# STM32-G0-Dip-Module.net
KiCad netlist of a schematic drawn in EAGLE
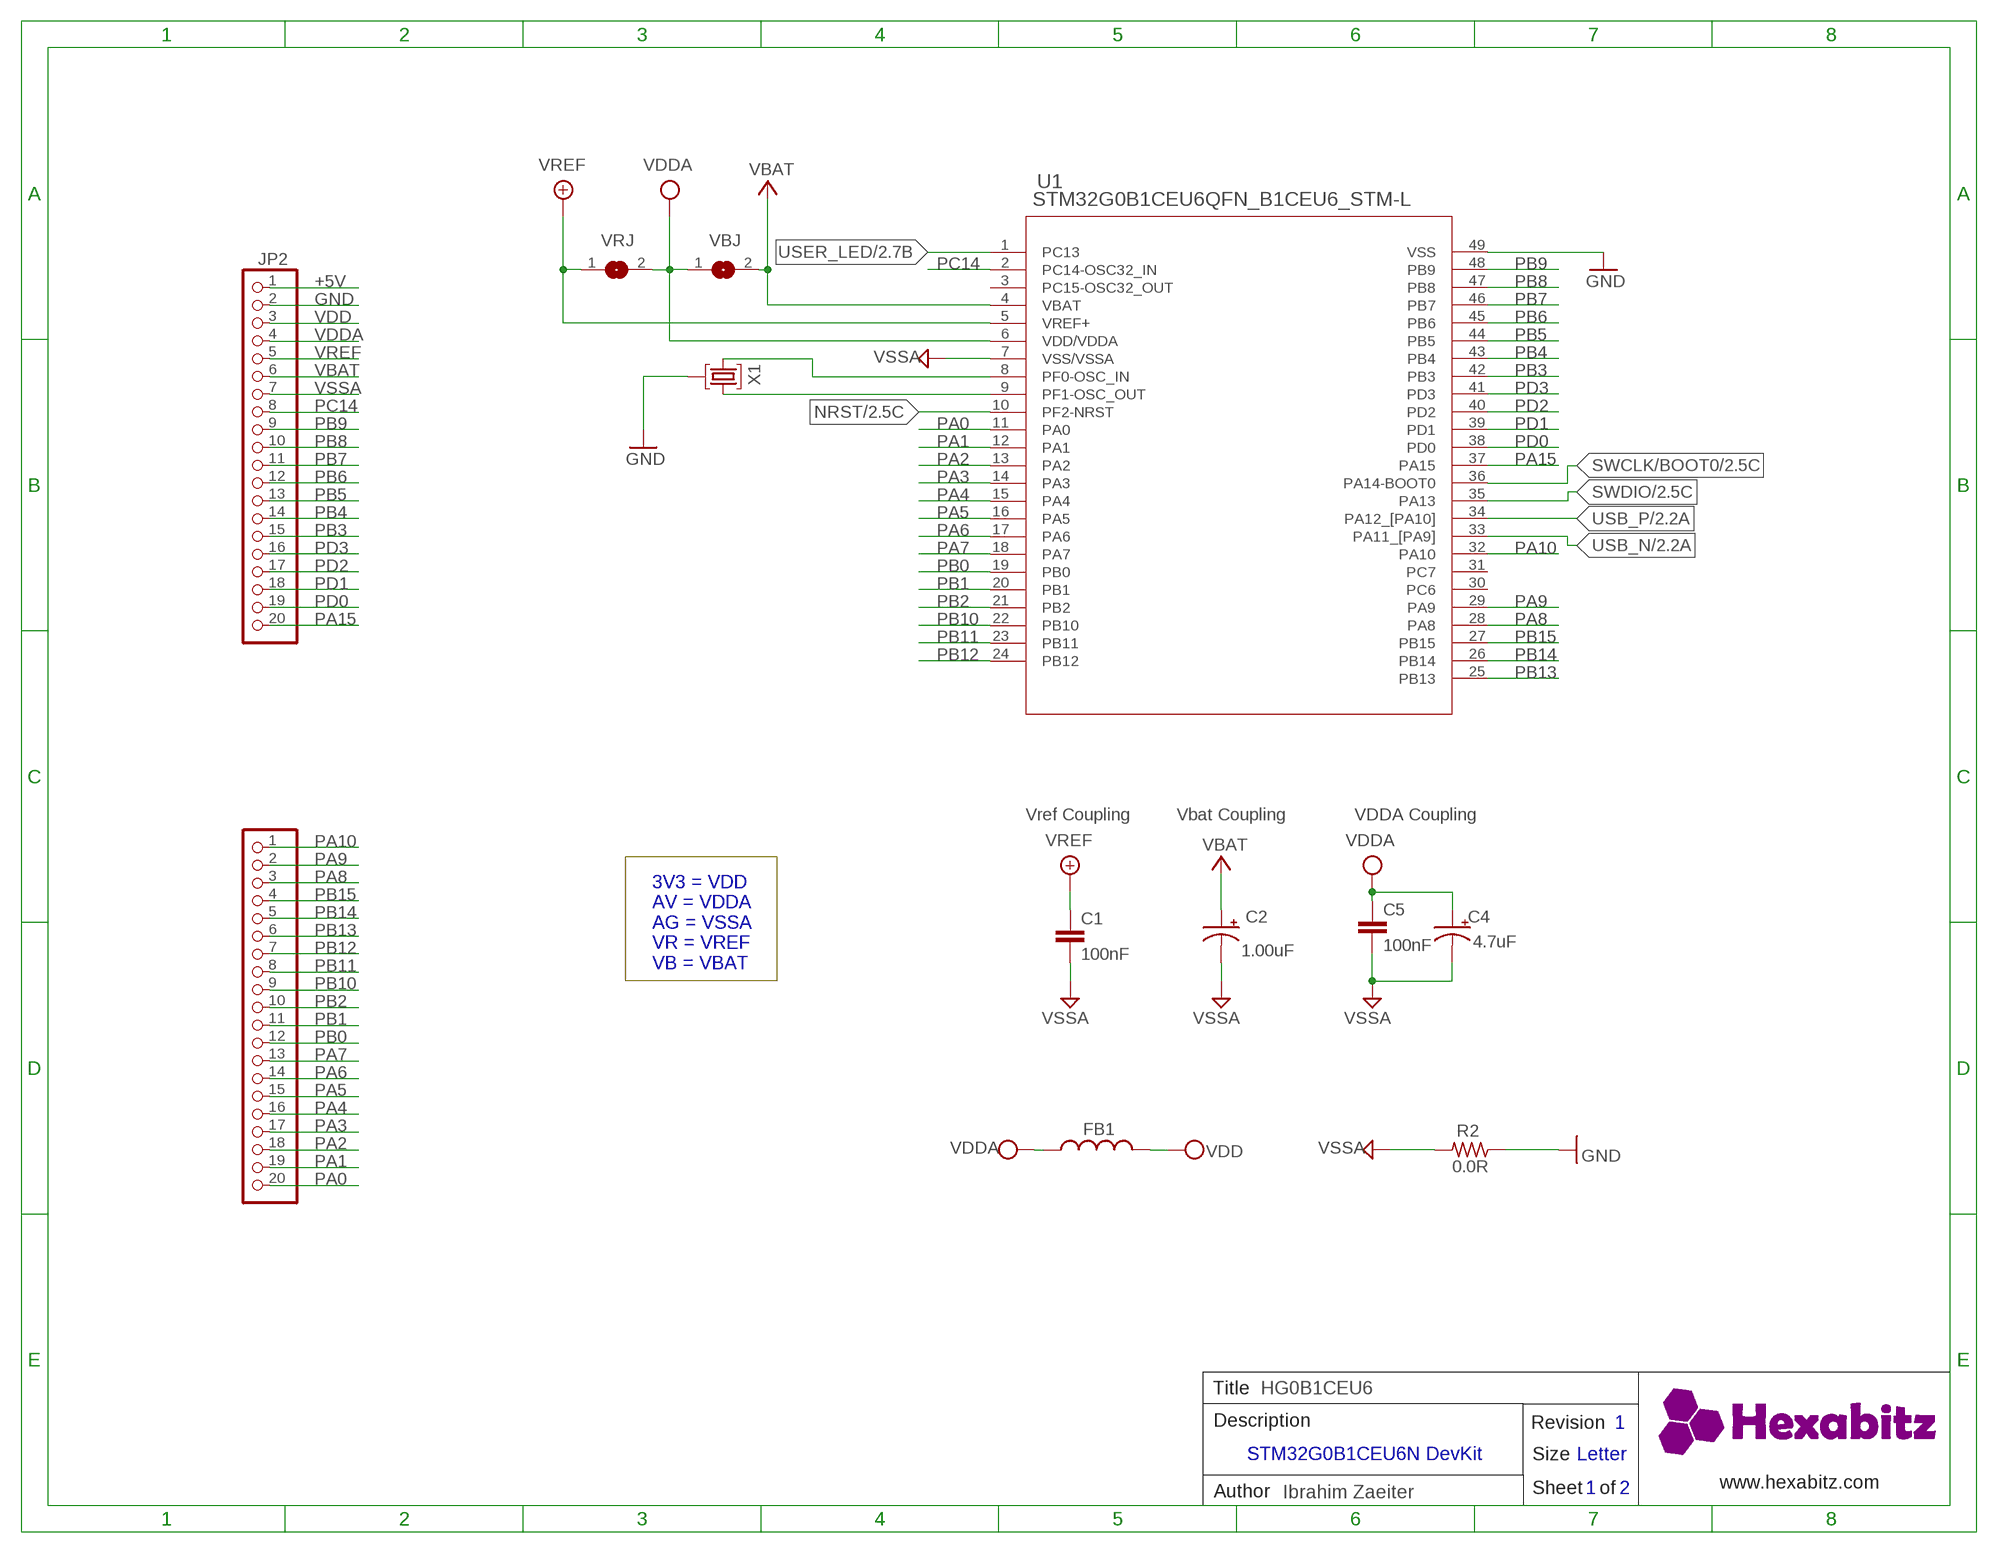
[diagram p0: schematic, sheet 1]
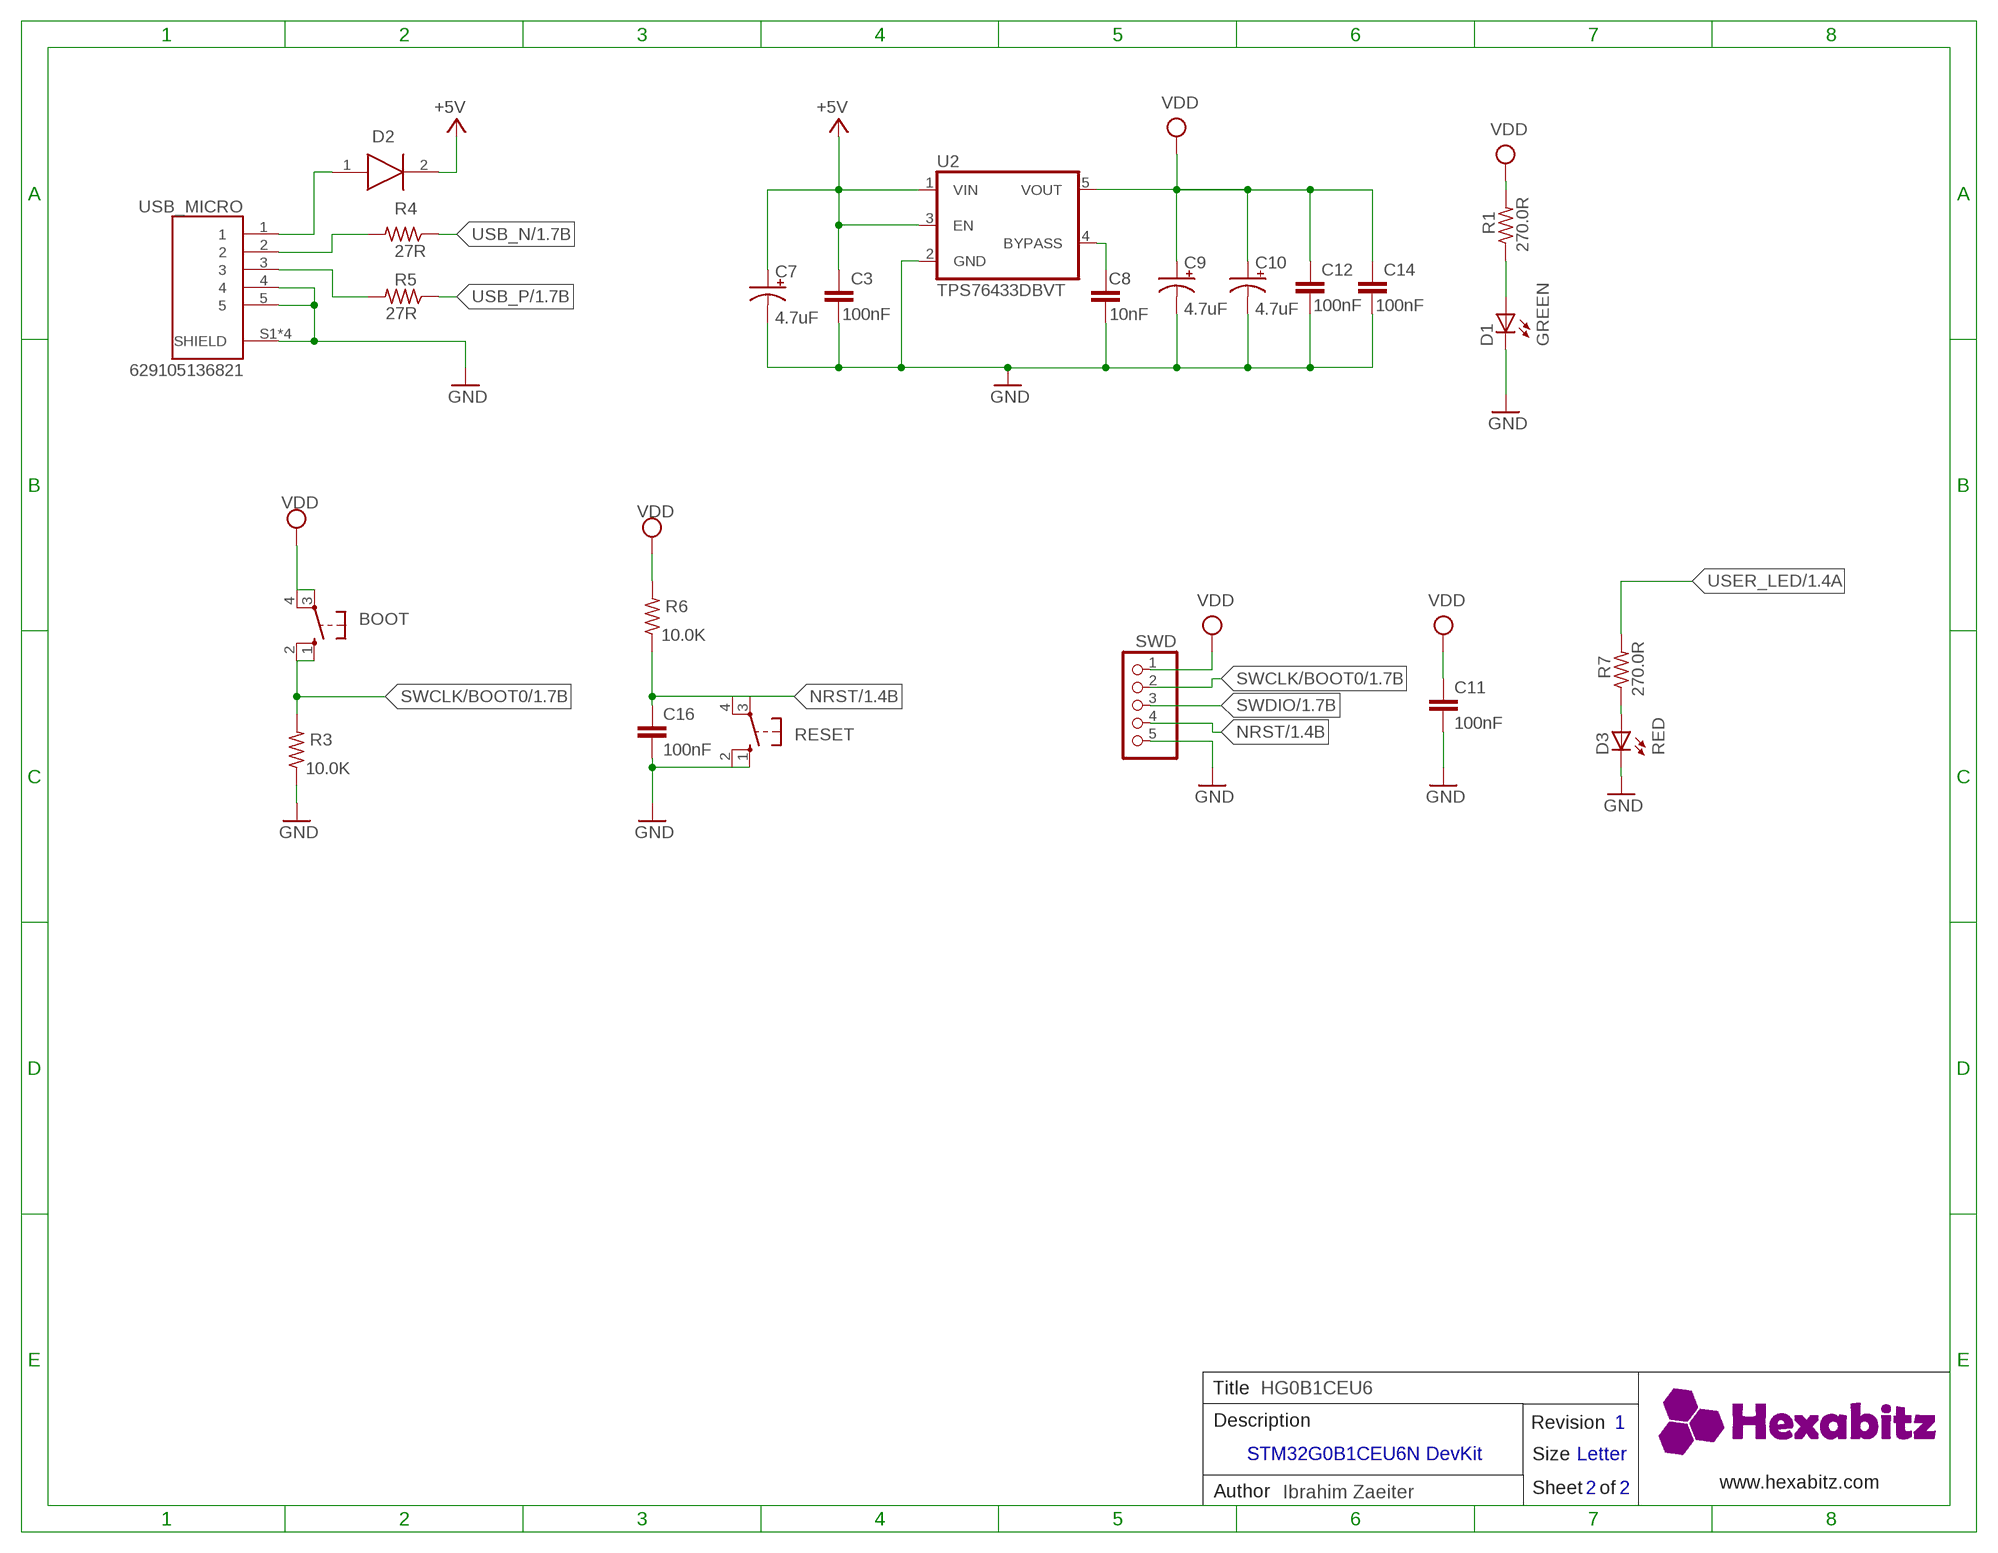
[diagram p1: schematic, sheet 2]

(export (version "E")
  (design (tool "Eeschema 10.0.6"))
  (components
    (comp (ref "C1")
      (value "100nF")
      (footprint "eagle-import:C-0603")
      (fields
        (field (name "CAPACITANCE") "100nF")
        (field (name "MFN") "KEMET")
        (field (name "MPN") "C0603C104K8RACTU")
        (field (name "OCTOPART_URL") "https://octopart.com/c0603c104k8ractu-kemet-145075?r=sp&s=9bS9ASSwSEqMCE9KBEQZ0g")
        (field (name "TOLERANCE") "10%")
        (field (name "VOLTAGE_RATING") "10V")
      )
      (libsource (lib "eagle-import") (part "C-0603"))
    )
    (comp (ref "C2")
      (value "1.00uF")
      (footprint "eagle-import:C-0805-POL")
      (fields
        (field (name "CAPACITANCE") "1.00uF")
        (field (name "MFN") "Yageo")
        (field (name "MPN") "CC0805KKX7R7BB105")
        (field (name "OCTOPART_URL") "https://octopart.com/cc0805kkx7r7bb105-yageo-8376555?r=sp&s=YKl1wwtkROau_X5nniH2ig")
        (field (name "TOLERANCE") "10%")
        (field (name "VOLTAGE_RATING") "16V")
      )
      (libsource (lib "eagle-import") (part "C-0805-POL"))
    )
    (comp (ref "C4")
      (value "4.7uF")
      (footprint "eagle-import:C-0805-POL")
      (fields
        (field (name "CAPACITANCE") "4.7uF")
        (field (name "MFN") "Murata")
        (field (name "MPN") "GRM21BC81E475KA12L")
        (field (name "OCTOPART_URL") "https://octopart.com/grm21bc81e475ka12l-murata-10331911?r=sp&s=RY3qZSD8T6mG6TC9CHI5qQ")
        (field (name "TOLERANCE") "10%")
        (field (name "VOLTAGE_RATING") "25V")
      )
      (libsource (lib "eagle-import") (part "C-0805-POL"))
    )
    (comp (ref "C5")
      (value "100nF")
      (footprint "eagle-import:C-0603")
      (fields
        (field (name "CAPACITANCE") "100nF")
        (field (name "MFN") "KEMET")
        (field (name "MPN") "C0603C104K8RACTU")
        (field (name "OCTOPART_URL") "https://octopart.com/c0603c104k8ractu-kemet-145075?r=sp&s=9bS9ASSwSEqMCE9KBEQZ0g")
        (field (name "TOLERANCE") "10%")
        (field (name "VOLTAGE_RATING") "10")
      )
      (libsource (lib "eagle-import") (part "C-0603"))
    )
    (comp (ref "FB1")
      (value "FB-TDK_MMZ1608Y300B")
      (footprint "eagle-import:FB-TDK_MMZ1608Y300B")
      (fields
        (field (name "MFN") "TDK ")
        (field (name "MPN") "MMZ1608Y300B")
        (field (name "OCTOPART_URL") "https://octopart.com/mmz1608y300b-tdk-368280?r=sp&s=cd9_2ZEqQ9q9UNBuQgHAiA")
      )
      (libsource (lib "eagle-import") (part "FB-TDK_MMZ1608Y300B"))
    )
    (comp (ref "JP1")
      (value "PINHD-1X20")
      (footprint "eagle-import:1X20")
      (libsource (lib "eagle-import") (part "PINHD-1X20"))
    )
    (comp (ref "JP2")
      (value "PINHD-1X20")
      (footprint "eagle-import:1X20")
      (libsource (lib "eagle-import") (part "PINHD-1X20"))
    )
    (comp (ref "R2")
      (value "0.0R")
      (footprint "eagle-import:R-0603")
      (fields
        (field (name "MFN") "Yageo")
        (field (name "MPN") "RC0603JR-070RL")
        (field (name "OCTOPART_URL") "https://octopart.com/rc0603jr-070rl-yageo-1241539?r=sp&s=X2NteqRjRNWrnx42Y0aliA")
        (field (name "RESISTANCE") "0.0 Ohm")
      )
      (libsource (lib "eagle-import") (part "R-0603"))
    )
    (comp (ref "U1")
      (value "STM32G0B1CEU6QFN_B1CEU6_STM-L")
      (footprint "eagle-import:QFN_B1CEU6_STM-L")
      (fields
        (field (name "MANUFACTURER_PART_NUMBER") "STM32G0B1CEU6")
        (field (name "COPYRIGHT") "Copyright (C) 2021 Ultra Librarian. All rights reserved.")
      )
      (libsource (lib "eagle-import") (part "STM32G0B1CEU6QFN_B1CEU6_STM-L"))
    )
    (comp (ref "VBJ") (value "SJ") (footprint "eagle-import:SJ") (libsource (lib "eagle-import") (part "SJ")))
    (comp (ref "VRJ") (value "SJ") (footprint "eagle-import:SJ") (libsource (lib "eagle-import") (part "SJ")))
    (comp (ref "X1")
      (value "XTALL_CSTCE8M00G52")
      (footprint "eagle-import:XTALL_CSTCE8M00G52")
      (fields (field (name "MPN") "CSTCE8M00G52Z-R0"))
      (libsource (lib "eagle-import") (part "XTALL_CSTCE8M00G52"))
    )
    (comp (ref "BOOT")
      (value "10-XX")
      (footprint "eagle-import:B3F-10XX")
      (fields (field (name "MPN") "B3F-1000"))
      (libsource (lib "eagle-import") (part "10-XX"))
    )
    (comp (ref "C3")
      (value "100nF")
      (footprint "eagle-import:C-0603")
      (fields
        (field (name "CAPACITANCE") "100nF")
        (field (name "MFN") "KEMET")
        (field (name "MPN") "C0603C104K8RACTU")
        (field (name "OCTOPART_URL") "https://octopart.com/c0603c104k8ractu-kemet-145075?r=sp&s=9bS9ASSwSEqMCE9KBEQZ0g")
        (field (name "TOLERANCE") "10%")
        (field (name "VOLTAGE_RATING") "10")
      )
      (libsource (lib "eagle-import") (part "C-0603"))
    )
    (comp (ref "C7")
      (value "4.7uF")
      (footprint "eagle-import:C-0805-POL")
      (fields
        (field (name "CAPACITANCE") "4.7uF")
        (field (name "MFN") "Murata")
        (field (name "MPN") "GRM21BC81E475KA12L")
        (field (name "OCTOPART_URL") "https://octopart.com/grm21bc81e475ka12l-murata-10331911?r=sp&s=RY3qZSD8T6mG6TC9CHI5qQ")
        (field (name "TOLERANCE") "10%")
        (field (name "VOLTAGE_RATING") "25V")
      )
      (libsource (lib "eagle-import") (part "C-0805-POL"))
    )
    (comp (ref "C8")
      (value "10nF")
      (footprint "eagle-import:C-0603")
      (fields
        (field (name "CAPACITANCE") "100nF")
        (field (name "MFN") "KEMET")
        (field (name "MPN") "C0603C104K8RACTU")
        (field (name "OCTOPART_URL") "https://octopart.com/c0603c104k8ractu-kemet-145075?r=sp&s=9bS9ASSwSEqMCE9KBEQZ0g")
        (field (name "TOLERANCE") "10%")
        (field (name "VOLTAGE_RATING") "10")
      )
      (libsource (lib "eagle-import") (part "C-0603"))
    )
    (comp (ref "C9")
      (value "4.7uF")
      (footprint "eagle-import:C-0805-POL")
      (fields
        (field (name "CAPACITANCE") "4.7uF")
        (field (name "MFN") "Murata")
        (field (name "MPN") "GRM21BC81E475KA12L")
        (field (name "OCTOPART_URL") "https://octopart.com/grm21bc81e475ka12l-murata-10331911?r=sp&s=RY3qZSD8T6mG6TC9CHI5qQ")
        (field (name "TOLERANCE") "10%")
        (field (name "VOLTAGE_RATING") "25V")
      )
      (libsource (lib "eagle-import") (part "C-0805-POL"))
    )
    (comp (ref "C10")
      (value "4.7uF")
      (footprint "eagle-import:C-0805-POL")
      (fields
        (field (name "CAPACITANCE") "4.7uF")
        (field (name "MFN") "Murata")
        (field (name "MPN") "GRM21BC81E475KA12L")
        (field (name "OCTOPART_URL") "https://octopart.com/grm21bc81e475ka12l-murata-10331911?r=sp&s=RY3qZSD8T6mG6TC9CHI5qQ")
        (field (name "TOLERANCE") "10%")
        (field (name "VOLTAGE_RATING") "25V")
      )
      (libsource (lib "eagle-import") (part "C-0805-POL"))
    )
    (comp (ref "C11")
      (value "100nF")
      (footprint "eagle-import:C-0603")
      (fields
        (field (name "CAPACITANCE") "100nF")
        (field (name "MFN") "KEMET")
        (field (name "MPN") "C0603C104K8RACTU")
        (field (name "OCTOPART_URL") "https://octopart.com/c0603c104k8ractu-kemet-145075?r=sp&s=9bS9ASSwSEqMCE9KBEQZ0g")
        (field (name "TOLERANCE") "10%")
        (field (name "VOLTAGE_RATING") "10V")
      )
      (libsource (lib "eagle-import") (part "C-0603"))
    )
    (comp (ref "C12")
      (value "100nF")
      (footprint "eagle-import:C-0603")
      (fields
        (field (name "CAPACITANCE") "100nF")
        (field (name "MFN") "KEMET")
        (field (name "MPN") "C0603C104K8RACTU")
        (field (name "OCTOPART_URL") "https://octopart.com/c0603c104k8ractu-kemet-145075?r=sp&s=9bS9ASSwSEqMCE9KBEQZ0g")
        (field (name "TOLERANCE") "10%")
        (field (name "VOLTAGE_RATING") "10")
      )
      (libsource (lib "eagle-import") (part "C-0603"))
    )
    (comp (ref "C14")
      (value "100nF")
      (footprint "eagle-import:C-0603")
      (fields
        (field (name "CAPACITANCE") "100nF")
        (field (name "MFN") "KEMET")
        (field (name "MPN") "C0603C104K8RACTU")
        (field (name "OCTOPART_URL") "https://octopart.com/c0603c104k8ractu-kemet-145075?r=sp&s=9bS9ASSwSEqMCE9KBEQZ0g")
        (field (name "TOLERANCE") "10%")
        (field (name "VOLTAGE_RATING") "10")
      )
      (libsource (lib "eagle-import") (part "C-0603"))
    )
    (comp (ref "C16")
      (value "100nF")
      (footprint "eagle-import:C-0603")
      (fields
        (field (name "CAPACITANCE") "100nF")
        (field (name "MFN") "KEMET")
        (field (name "MPN") "C0603C104K8RACTU")
        (field (name "OCTOPART_URL") "https://octopart.com/c0603c104k8ractu-kemet-145075?r=sp&s=9bS9ASSwSEqMCE9KBEQZ0g")
        (field (name "TOLERANCE") "10%")
        (field (name "VOLTAGE_RATING") "10V")
      )
      (libsource (lib "eagle-import") (part "C-0603"))
    )
    (comp (ref "D1")
      (value "GREEN")
      (footprint "eagle-import:VLMS1300-GS08")
      (fields
        (field (name "MPN") "VLMS1300-GS08")
        (field (name "MFN") "Vishay")
        (field (name "MPN_1") "VLMS1300-GS08")
        (field (name "OCTOPART_URL") "https://octopart.com/vlms1300-gs08-vishay-21709201?r=sp&s=_gcP4_q8T1SC6PJQPTQ9yA")
      )
      (libsource (lib "eagle-import") (part "VLMS1300-GS08"))
    )
    (comp (ref "D2")
      (value "FSM17PL-TP")
      (footprint "eagle-import:FSM17PL-TP")
      (libsource (lib "eagle-import") (part "FSM17PL-TP"))
    )
    (comp (ref "D3")
      (value "RED")
      (footprint "eagle-import:VLMS1300-GS08")
      (fields
        (field (name "MPN") "VLMS1300-GS08")
        (field (name "MFN") "Vishay")
        (field (name "MPN_1") "VLMS1300-GS08")
        (field (name "OCTOPART_URL") "https://octopart.com/vlms1300-gs08-vishay-21709201?r=sp&s=_gcP4_q8T1SC6PJQPTQ9yA")
      )
      (libsource (lib "eagle-import") (part "VLMS1300-GS08"))
    )
    (comp (ref "R1")
      (value "270.0R")
      (footprint "eagle-import:R-0603")
      (fields
        (field (name "MFN") "Yageo")
        (field (name "MPN") "RC0603FR-07270RL")
        (field (name "OCTOPART_URL") "https://octopart.com/search?q=RC0603FR-07270RL&start=0")
        (field (name "RESISTANCE") "270.0 Ohm")
        (field (name "TOLERANCE") "1%")
      )
      (libsource (lib "eagle-import") (part "R-0603"))
    )
    (comp (ref "R3")
      (value "10.0K")
      (footprint "eagle-import:R-0603")
      (fields
        (field (name "MFN") "Yageo")
        (field (name "MPN") "RC0603JR-0710KL")
        (field (name "OCTOPART_URL") "https://octopart.com/search?q=RC0603JR-0710KL&start=0")
        (field (name "RESISTANCE") "10.0K Ohm")
        (field (name "TOLERANCE") "5%")
      )
      (libsource (lib "eagle-import") (part "R-0603"))
    )
    (comp (ref "R4")
      (value "27R")
      (footprint "eagle-import:R-0603")
      (fields
        (field (name "MFN") "Yageo")
        (field (name "MPN") "RC0603JR-0710KL")
        (field (name "OCTOPART_URL") "https://octopart.com/search?q=RC0603JR-0710KL&start=0")
        (field (name "RESISTANCE") "10.0K Ohm")
        (field (name "TOLERANCE") "5%")
      )
      (libsource (lib "eagle-import") (part "R-0603"))
    )
    (comp (ref "R5")
      (value "27R")
      (footprint "eagle-import:R-0603")
      (fields
        (field (name "MFN") "Yageo")
        (field (name "MPN") "RC0603JR-0710KL")
        (field (name "OCTOPART_URL") "https://octopart.com/search?q=RC0603JR-0710KL&start=0")
        (field (name "RESISTANCE") "10.0K Ohm")
        (field (name "TOLERANCE") "5%")
      )
      (libsource (lib "eagle-import") (part "R-0603"))
    )
    (comp (ref "R6")
      (value "10.0K")
      (footprint "eagle-import:R-0603")
      (fields
        (field (name "MFN") "Yageo")
        (field (name "MPN") "RC0603JR-0710KL")
        (field (name "OCTOPART_URL") "https://octopart.com/search?q=RC0603JR-0710KL&start=0")
        (field (name "RESISTANCE") "10.0K Ohm")
        (field (name "TOLERANCE") "5%")
      )
      (libsource (lib "eagle-import") (part "R-0603"))
    )
    (comp (ref "R7")
      (value "270.0R")
      (footprint "eagle-import:R-0603")
      (fields
        (field (name "MFN") "Yageo")
        (field (name "MPN") "RC0603FR-07270RL")
        (field (name "OCTOPART_URL") "https://octopart.com/search?q=RC0603FR-07270RL&start=0")
        (field (name "RESISTANCE") "270.0 Ohm")
        (field (name "TOLERANCE") "1%")
      )
      (libsource (lib "eagle-import") (part "R-0603"))
    )
    (comp (ref "RESET")
      (value "10-XX")
      (footprint "eagle-import:B3F-10XX")
      (fields (field (name "MPN") "B3F-1000"))
      (libsource (lib "eagle-import") (part "10-XX"))
    )
    (comp (ref "SWD")
      (value "PINHD-1X5/90")
      (footprint "eagle-import:1X05_90")
      (libsource (lib "eagle-import") (part "PINHD-1X5/90"))
    )
    (comp (ref "U2")
      (value "TPS76433DBVT")
      (footprint "eagle-import:SOT25")
      (libsource (lib "eagle-import") (part "TPS764DBVT33"))
    )
    (comp (ref "USB_MICRO")
      (value "629105136821")
      (footprint "eagle-import:WE_629105136821")
      (fields (field (name "MF") "Würth Elektronik"))
      (libsource (lib "eagle-import") (part "629105136821"))
    )
  )
  (nets
    (net (code "1") (name "+5V") (class "Default")
      (node (ref "C3") (pin "1") (pinfunction "1_1") (pintype "passive"))
      (node (ref "C7") (pin "1") (pinfunction "+_1") (pintype "passive"))
      (node (ref "D2") (pin "2") (pinfunction "K_2") (pintype "bidirectional"))
      (node (ref "JP2") (pin "1") (pinfunction "1_1") (pintype "passive"))
      (node (ref "U2") (pin "1") (pinfunction "VIN_1") (pintype "input"))
      (node (ref "U2") (pin "3") (pinfunction "EN_3") (pintype "input"))
    )
    (net (code "2") (name "GND") (class "Default")
      (node (ref "C10") (pin "2") (pinfunction "-_2") (pintype "passive"))
      (node (ref "C11") (pin "2") (pinfunction "2_2") (pintype "passive"))
      (node (ref "C12") (pin "2") (pinfunction "2_2") (pintype "passive"))
      (node (ref "C14") (pin "2") (pinfunction "2_2") (pintype "passive"))
      (node (ref "C16") (pin "2") (pinfunction "2_2") (pintype "passive"))
      (node (ref "C3") (pin "2") (pinfunction "2_2") (pintype "passive"))
      (node (ref "C7") (pin "2") (pinfunction "-_2") (pintype "passive"))
      (node (ref "C8") (pin "2") (pinfunction "2_2") (pintype "passive"))
      (node (ref "C9") (pin "2") (pinfunction "-_2") (pintype "passive"))
      (node (ref "D1") (pin "C") (pinfunction "C_C") (pintype "passive"))
      (node (ref "D3") (pin "C") (pinfunction "C_C") (pintype "passive"))
      (node (ref "JP2") (pin "2") (pinfunction "2_2") (pintype "passive"))
      (node (ref "R2") (pin "1") (pinfunction "1_1") (pintype "passive"))
      (node (ref "R3") (pin "1") (pinfunction "1_1") (pintype "passive"))
      (node (ref "RESET") (pin "1") (pinfunction "S_1") (pintype "passive"))
      (node (ref "RESET") (pin "2") (pinfunction "S1_2") (pintype "passive"))
      (node (ref "SWD") (pin "5") (pinfunction "5_5") (pintype "passive"))
      (node (ref "U1") (pin "49") (pinfunction "VSS_49") (pintype "passive"))
      (node (ref "U2") (pin "2") (pinfunction "GND_2") (pintype "passive"))
      (node (ref "USB_MICRO") (pin "4") (pinfunction "4_4") (pintype "passive"))
      (node (ref "USB_MICRO") (pin "5") (pinfunction "5_5") (pintype "passive"))
      (node (ref "USB_MICRO") (pin "S1") (pinfunction "SHIELD_S1") (pintype "passive"))
      (node (ref "USB_MICRO") (pin "S2") (pinfunction "SHIELD_S2") (pintype "passive"))
      (node (ref "USB_MICRO") (pin "S3") (pinfunction "SHIELD_S3") (pintype "passive"))
      (node (ref "USB_MICRO") (pin "S4") (pinfunction "SHIELD_S4") (pintype "passive"))
      (node (ref "X1") (pin "P$2") (pinfunction "2_P$2") (pintype "passive"))
    )
    (net (code "3") (name "NRST") (class "Default")
      (node (ref "C16") (pin "1") (pinfunction "1_1") (pintype "passive"))
      (node (ref "R6") (pin "1") (pinfunction "1_1") (pintype "passive"))
      (node (ref "RESET") (pin "3") (pinfunction "P_3") (pintype "passive"))
      (node (ref "RESET") (pin "4") (pinfunction "P1_4") (pintype "passive"))
      (node (ref "SWD") (pin "4") (pinfunction "4_4") (pintype "passive"))
      (node (ref "U1") (pin "10") (pinfunction "PF2-NRST_10") (pintype "bidirectional"))
    )
    (net (code "4") (name "Net-(D1-PadA)") (class "Default")
      (node (ref "D1") (pin "A") (pinfunction "A_A") (pintype "passive"))
      (node (ref "R1") (pin "1") (pinfunction "1_1") (pintype "passive"))
    )
    (net (code "5") (name "Net-(D2-A)") (class "Default")
      (node (ref "D2") (pin "1") (pinfunction "A_1") (pintype "bidirectional"))
      (node (ref "USB_MICRO") (pin "1") (pinfunction "1_1") (pintype "passive"))
    )
    (net (code "6") (name "Net-(D3-PadA)") (class "Default")
      (node (ref "D3") (pin "A") (pinfunction "A_A") (pintype "passive"))
      (node (ref "R7") (pin "1") (pinfunction "1_1") (pintype "passive"))
    )
    (net (code "7") (name "Net-(R4-Pad2)") (class "Default")
      (node (ref "R4") (pin "2") (pinfunction "2_2") (pintype "passive"))
      (node (ref "USB_MICRO") (pin "2") (pinfunction "2_2") (pintype "passive"))
    )
    (net (code "8") (name "Net-(R5-Pad2)") (class "Default")
      (node (ref "R5") (pin "2") (pinfunction "2_2") (pintype "passive"))
      (node (ref "USB_MICRO") (pin "3") (pinfunction "3_3") (pintype "passive"))
    )
    (net (code "9") (name "Net-(U1-PF0-OSC_IN)") (class "Default")
      (node (ref "U1") (pin "8") (pinfunction "PF0-OSC_IN_8") (pintype "bidirectional"))
      (node (ref "X1") (pin "P$1") (pinfunction "1_P$1") (pintype "passive"))
    )
    (net (code "10") (name "Net-(U1-PF1-OSC_OUT)") (class "Default")
      (node (ref "U1") (pin "9") (pinfunction "PF1-OSC_OUT_9") (pintype "output"))
      (node (ref "X1") (pin "P$3") (pinfunction "3_P$3") (pintype "passive"))
    )
    (net (code "11") (name "Net-(U2-BYPASS)") (class "Default")
      (node (ref "C8") (pin "1") (pinfunction "1_1") (pintype "passive"))
      (node (ref "U2") (pin "4") (pinfunction "BYPASS_4") (pintype "input"))
    )
    (net (code "12") (name "PA0") (class "Default")
      (node (ref "JP1") (pin "20") (pinfunction "20_20") (pintype "passive"))
      (node (ref "U1") (pin "11") (pinfunction "PA0_11") (pintype "bidirectional"))
    )
    (net (code "13") (name "PA1") (class "Default")
      (node (ref "JP1") (pin "19") (pinfunction "19_19") (pintype "passive"))
      (node (ref "U1") (pin "12") (pinfunction "PA1_12") (pintype "bidirectional"))
    )
    (net (code "14") (name "PA2") (class "Default")
      (node (ref "JP1") (pin "18") (pinfunction "18_18") (pintype "passive"))
      (node (ref "U1") (pin "13") (pinfunction "PA2_13") (pintype "bidirectional"))
    )
    (net (code "15") (name "PA3") (class "Default")
      (node (ref "JP1") (pin "17") (pinfunction "17_17") (pintype "passive"))
      (node (ref "U1") (pin "14") (pinfunction "PA3_14") (pintype "bidirectional"))
    )
    (net (code "16") (name "PA4") (class "Default")
      (node (ref "JP1") (pin "16") (pinfunction "16_16") (pintype "passive"))
      (node (ref "U1") (pin "15") (pinfunction "PA4_15") (pintype "bidirectional"))
    )
    (net (code "17") (name "PA5") (class "Default")
      (node (ref "JP1") (pin "15") (pinfunction "15_15") (pintype "passive"))
      (node (ref "U1") (pin "16") (pinfunction "PA5_16") (pintype "bidirectional"))
    )
    (net (code "18") (name "PA6") (class "Default")
      (node (ref "JP1") (pin "14") (pinfunction "14_14") (pintype "passive"))
      (node (ref "U1") (pin "17") (pinfunction "PA6_17") (pintype "bidirectional"))
    )
    (net (code "19") (name "PA7") (class "Default")
      (node (ref "JP1") (pin "13") (pinfunction "13_13") (pintype "passive"))
      (node (ref "U1") (pin "18") (pinfunction "PA7_18") (pintype "bidirectional"))
    )
    (net (code "20") (name "PA8") (class "Default")
      (node (ref "JP1") (pin "3") (pinfunction "3_3") (pintype "passive"))
      (node (ref "U1") (pin "28") (pinfunction "PA8_28") (pintype "bidirectional"))
    )
    (net (code "21") (name "PA9") (class "Default")
      (node (ref "JP1") (pin "2") (pinfunction "2_2") (pintype "passive"))
      (node (ref "U1") (pin "29") (pinfunction "PA9_29") (pintype "bidirectional"))
    )
    (net (code "22") (name "PA10") (class "Default")
      (node (ref "JP1") (pin "1") (pinfunction "1_1") (pintype "passive"))
      (node (ref "U1") (pin "32") (pinfunction "PA10_32") (pintype "bidirectional"))
    )
    (net (code "23") (name "PA15") (class "Default")
      (node (ref "JP2") (pin "20") (pinfunction "20_20") (pintype "passive"))
      (node (ref "U1") (pin "37") (pinfunction "PA15_37") (pintype "bidirectional"))
    )
    (net (code "24") (name "PB0") (class "Default")
      (node (ref "JP1") (pin "12") (pinfunction "12_12") (pintype "passive"))
      (node (ref "U1") (pin "19") (pinfunction "PB0_19") (pintype "bidirectional"))
    )
    (net (code "25") (name "PB1") (class "Default")
      (node (ref "JP1") (pin "11") (pinfunction "11_11") (pintype "passive"))
      (node (ref "U1") (pin "20") (pinfunction "PB1_20") (pintype "bidirectional"))
    )
    (net (code "26") (name "PB2") (class "Default")
      (node (ref "JP1") (pin "10") (pinfunction "10_10") (pintype "passive"))
      (node (ref "U1") (pin "21") (pinfunction "PB2_21") (pintype "bidirectional"))
    )
    (net (code "27") (name "PB3") (class "Default")
      (node (ref "JP2") (pin "15") (pinfunction "15_15") (pintype "passive"))
      (node (ref "U1") (pin "42") (pinfunction "PB3_42") (pintype "bidirectional"))
    )
    (net (code "28") (name "PB4") (class "Default")
      (node (ref "JP2") (pin "14") (pinfunction "14_14") (pintype "passive"))
      (node (ref "U1") (pin "43") (pinfunction "PB4_43") (pintype "bidirectional"))
    )
    (net (code "29") (name "PB5") (class "Default")
      (node (ref "JP2") (pin "13") (pinfunction "13_13") (pintype "passive"))
      (node (ref "U1") (pin "44") (pinfunction "PB5_44") (pintype "bidirectional"))
    )
    (net (code "30") (name "PB6") (class "Default")
      (node (ref "JP2") (pin "12") (pinfunction "12_12") (pintype "passive"))
      (node (ref "U1") (pin "45") (pinfunction "PB6_45") (pintype "bidirectional"))
    )
    (net (code "31") (name "PB7") (class "Default")
      (node (ref "JP2") (pin "11") (pinfunction "11_11") (pintype "passive"))
      (node (ref "U1") (pin "46") (pinfunction "PB7_46") (pintype "bidirectional"))
    )
    (net (code "32") (name "PB8") (class "Default")
      (node (ref "JP2") (pin "10") (pinfunction "10_10") (pintype "passive"))
      (node (ref "U1") (pin "47") (pinfunction "PB8_47") (pintype "bidirectional"))
    )
    (net (code "33") (name "PB9") (class "Default")
      (node (ref "JP2") (pin "9") (pinfunction "9_9") (pintype "passive"))
      (node (ref "U1") (pin "48") (pinfunction "PB9_48") (pintype "bidirectional"))
    )
    (net (code "34") (name "PB10") (class "Default")
      (node (ref "JP1") (pin "9") (pinfunction "9_9") (pintype "passive"))
      (node (ref "U1") (pin "22") (pinfunction "PB10_22") (pintype "bidirectional"))
    )
    (net (code "35") (name "PB11") (class "Default")
      (node (ref "JP1") (pin "8") (pinfunction "8_8") (pintype "passive"))
      (node (ref "U1") (pin "23") (pinfunction "PB11_23") (pintype "bidirectional"))
    )
    (net (code "36") (name "PB12") (class "Default")
      (node (ref "JP1") (pin "7") (pinfunction "7_7") (pintype "passive"))
      (node (ref "U1") (pin "24") (pinfunction "PB12_24") (pintype "bidirectional"))
    )
    (net (code "37") (name "PB13") (class "Default")
      (node (ref "JP1") (pin "6") (pinfunction "6_6") (pintype "passive"))
      (node (ref "U1") (pin "25") (pinfunction "PB13_25") (pintype "bidirectional"))
    )
    (net (code "38") (name "PB14") (class "Default")
      (node (ref "JP1") (pin "5") (pinfunction "5_5") (pintype "passive"))
      (node (ref "U1") (pin "26") (pinfunction "PB14_26") (pintype "bidirectional"))
    )
    (net (code "39") (name "PB15") (class "Default")
      (node (ref "JP1") (pin "4") (pinfunction "4_4") (pintype "passive"))
      (node (ref "U1") (pin "27") (pinfunction "PB15_27") (pintype "bidirectional"))
    )
    (net (code "40") (name "PC14") (class "Default")
      (node (ref "JP2") (pin "8") (pinfunction "8_8") (pintype "passive"))
      (node (ref "U1") (pin "2") (pinfunction "PC14-OSC32_IN_2") (pintype "bidirectional"))
    )
    (net (code "41") (name "PD0") (class "Default")
      (node (ref "JP2") (pin "19") (pinfunction "19_19") (pintype "passive"))
      (node (ref "U1") (pin "38") (pinfunction "PD0_38") (pintype "bidirectional"))
    )
    (net (code "42") (name "PD1") (class "Default")
      (node (ref "JP2") (pin "18") (pinfunction "18_18") (pintype "passive"))
      (node (ref "U1") (pin "39") (pinfunction "PD1_39") (pintype "bidirectional"))
    )
    (net (code "43") (name "PD2") (class "Default")
      (node (ref "JP2") (pin "17") (pinfunction "17_17") (pintype "passive"))
      (node (ref "U1") (pin "40") (pinfunction "PD2_40") (pintype "bidirectional"))
    )
    (net (code "44") (name "PD3") (class "Default")
      (node (ref "JP2") (pin "16") (pinfunction "16_16") (pintype "passive"))
      (node (ref "U1") (pin "41") (pinfunction "PD3_41") (pintype "bidirectional"))
    )
    (net (code "45") (name "SWCLK{slash}BOOT0") (class "Default")
      (node (ref "BOOT") (pin "1") (pinfunction "S_1") (pintype "passive"))
      (node (ref "BOOT") (pin "2") (pinfunction "S1_2") (pintype "passive"))
      (node (ref "R3") (pin "2") (pinfunction "2_2") (pintype "passive"))
      (node (ref "SWD") (pin "2") (pinfunction "2_2") (pintype "passive"))
      (node (ref "U1") (pin "36") (pinfunction "PA14-BOOT0_36") (pintype "bidirectional"))
    )
    (net (code "46") (name "SWDIO") (class "Default")
      (node (ref "SWD") (pin "3") (pinfunction "3_3") (pintype "passive"))
      (node (ref "U1") (pin "35") (pinfunction "PA13_35") (pintype "bidirectional"))
    )
    (net (code "47") (name "USB_N") (class "Default")
      (node (ref "R4") (pin "1") (pinfunction "1_1") (pintype "passive"))
      (node (ref "U1") (pin "33") (pinfunction "PA11_[PA9]_33") (pintype "bidirectional"))
    )
    (net (code "48") (name "USB_P") (class "Default")
      (node (ref "R5") (pin "1") (pinfunction "1_1") (pintype "passive"))
      (node (ref "U1") (pin "34") (pinfunction "PA12_[PA10]_34") (pintype "bidirectional"))
    )
    (net (code "49") (name "USER_LED") (class "Default")
      (node (ref "R7") (pin "2") (pinfunction "2_2") (pintype "passive"))
      (node (ref "U1") (pin "1") (pinfunction "PC13_1") (pintype "bidirectional"))
    )
    (net (code "50") (name "VBAT") (class "Default")
      (node (ref "C2") (pin "1") (pinfunction "+_1") (pintype "passive"))
      (node (ref "JP2") (pin "6") (pinfunction "6_6") (pintype "passive"))
      (node (ref "U1") (pin "4") (pinfunction "VBAT_4") (pintype "passive"))
      (node (ref "VBJ") (pin "2") (pinfunction "2_2") (pintype "passive"))
    )
    (net (code "51") (name "VDD") (class "Default")
      (node (ref "BOOT") (pin "3") (pinfunction "P_3") (pintype "passive"))
      (node (ref "BOOT") (pin "4") (pinfunction "P1_4") (pintype "passive"))
      (node (ref "C10") (pin "1") (pinfunction "+_1") (pintype "passive"))
      (node (ref "C11") (pin "1") (pinfunction "1_1") (pintype "passive"))
      (node (ref "C12") (pin "1") (pinfunction "1_1") (pintype "passive"))
      (node (ref "C14") (pin "1") (pinfunction "1_1") (pintype "passive"))
      (node (ref "C9") (pin "1") (pinfunction "+_1") (pintype "passive"))
      (node (ref "FB1") (pin "2") (pinfunction "2_2") (pintype "passive"))
      (node (ref "JP2") (pin "3") (pinfunction "3_3") (pintype "passive"))
      (node (ref "R1") (pin "2") (pinfunction "2_2") (pintype "passive"))
      (node (ref "R6") (pin "2") (pinfunction "2_2") (pintype "passive"))
      (node (ref "SWD") (pin "1") (pinfunction "1_1") (pintype "passive"))
      (node (ref "U2") (pin "5") (pinfunction "VOUT_5") (pintype "passive"))
    )
    (net (code "52") (name "VDDA") (class "Default")
      (node (ref "C4") (pin "1") (pinfunction "+_1") (pintype "passive"))
      (node (ref "C5") (pin "1") (pinfunction "1_1") (pintype "passive"))
      (node (ref "FB1") (pin "1") (pinfunction "1_1") (pintype "passive"))
      (node (ref "JP2") (pin "4") (pinfunction "4_4") (pintype "passive"))
      (node (ref "U1") (pin "6") (pinfunction "VDD/VDDA_6") (pintype "power_in"))
      (node (ref "VBJ") (pin "1") (pinfunction "1_1") (pintype "passive"))
      (node (ref "VRJ") (pin "2") (pinfunction "2_2") (pintype "passive"))
    )
    (net (code "53") (name "VREF") (class "Default")
      (node (ref "C1") (pin "1") (pinfunction "1_1") (pintype "passive"))
      (node (ref "JP2") (pin "5") (pinfunction "5_5") (pintype "passive"))
      (node (ref "U1") (pin "5") (pinfunction "VREF+_5") (pintype "power_in"))
      (node (ref "VRJ") (pin "1") (pinfunction "1_1") (pintype "passive"))
    )
    (net (code "54") (name "VSSA") (class "Default")
      (node (ref "C1") (pin "2") (pinfunction "2_2") (pintype "passive"))
      (node (ref "C2") (pin "2") (pinfunction "-_2") (pintype "passive"))
      (node (ref "C4") (pin "2") (pinfunction "-_2") (pintype "passive"))
      (node (ref "C5") (pin "2") (pinfunction "2_2") (pintype "passive"))
      (node (ref "JP2") (pin "7") (pinfunction "7_7") (pintype "passive"))
      (node (ref "R2") (pin "2") (pinfunction "2_2") (pintype "passive"))
      (node (ref "U1") (pin "7") (pinfunction "VSS/VSSA_7") (pintype "passive"))
    )
    (net (code "55") (name "unconnected-(U1-PC6-Pad30)") (class "Default")
      (node (ref "U1") (pin "30") (pinfunction "PC6_30") (pintype "bidirectional"))
    )
    (net (code "56") (name "unconnected-(U1-PC7-Pad31)") (class "Default")
      (node (ref "U1") (pin "31") (pinfunction "PC7_31") (pintype "bidirectional"))
    )
    (net (code "57") (name "unconnected-(U1-PC15-OSC32_OUT-Pad3)") (class "Default")
      (node (ref "U1") (pin "3") (pinfunction "PC15-OSC32_OUT_3") (pintype "output"))
    )
  )
)
